# I2C_Switch.net
KiCad netlist of a schematic drawn in Altium Designer
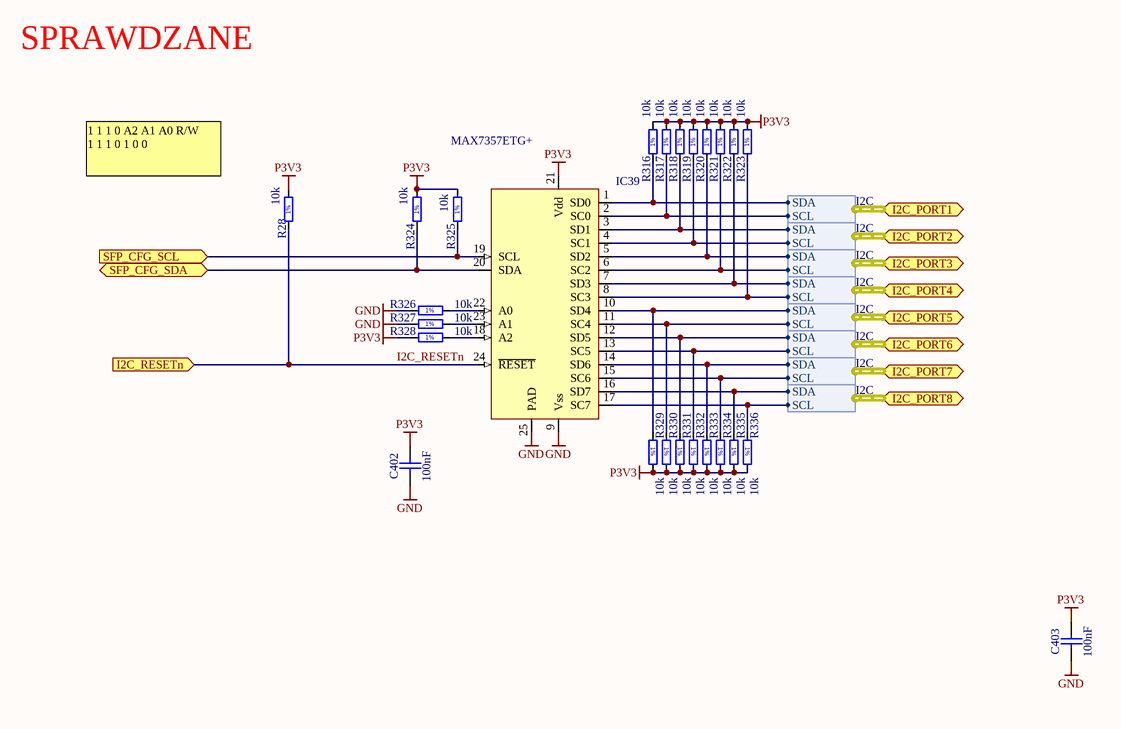
[diagram p0: I2C_Switch.SchDoc]

(export (version "E")
  (design (tool "Eeschema 10.0.6"))
  (components
    (comp (ref "C402")
      (value "100nF")
      (footprint "CAPC0603X33N")
      (description "Non-polarised capacitor")
      (fields
        (field (name "PART NUMBER") "CC0201_100NF_6.3V_10%_X5R")
        (field (name "VOLTAGE") "6.3V")
        (field (name "AUTHOR") "CERN DEM JLC")
      )
      (libsource (lib "Capacitors") (part "Capacitor - non polarized"))
    )
    (comp (ref "C403")
      (value "100nF")
      (footprint "CAPC0603X33N")
      (description "Non-polarised capacitor")
      (fields
        (field (name "PART NUMBER") "CC0201_100NF_6.3V_10%_X5R")
        (field (name "VOLTAGE") "6.3V")
        (field (name "AUTHOR") "CERN DEM JLC")
      )
      (libsource (lib "Capacitors") (part "Capacitor - non polarized"))
    )
    (comp (ref "IC39")
      (value "MAX7357ETG+")
      (footprint "HVQFN24")
      (description "8-channel I2C-bus multiplexer with reset, INT and timeout")
      (libsource (lib "LIBRARY_SCH") (part "IIC_MUX_MAX7357ETG+"))
    )
    (comp (ref "R28")
      (value "10k")
      (footprint "RESC1005X40N")
      (description "Resistor - 1%")
      (fields
        (field (name "PART NUMBER") "R0402_10K_1%_0.0625W_100PPM")
        (field (name "POWER") "0.0625W")
        (field (name "AUTHOR") "CERN DEM JLC")
      )
      (libsource (lib "Resistors") (part "Resistor - 1%"))
    )
    (comp (ref "R316")
      (value "10k")
      (footprint "RESC1005X40N")
      (description "Resistor - 1%")
      (fields
        (field (name "PART NUMBER") "R0402_10K_1%_0.0625W_100PPM")
        (field (name "POWER") "0.0625W")
        (field (name "AUTHOR") "CERN DEM JLC")
      )
      (libsource (lib "Resistors") (part "Resistor - 1%"))
    )
    (comp (ref "R317")
      (value "10k")
      (footprint "RESC1005X40N")
      (description "Resistor - 1%")
      (fields
        (field (name "PART NUMBER") "R0402_10K_1%_0.0625W_100PPM")
        (field (name "POWER") "0.0625W")
        (field (name "AUTHOR") "CERN DEM JLC")
      )
      (libsource (lib "Resistors") (part "Resistor - 1%"))
    )
    (comp (ref "R318")
      (value "10k")
      (footprint "RESC1005X40N")
      (description "Resistor - 1%")
      (fields
        (field (name "PART NUMBER") "R0402_10K_1%_0.0625W_100PPM")
        (field (name "POWER") "0.0625W")
        (field (name "AUTHOR") "CERN DEM JLC")
      )
      (libsource (lib "Resistors") (part "Resistor - 1%"))
    )
    (comp (ref "R319")
      (value "10k")
      (footprint "RESC1005X40N")
      (description "Resistor - 1%")
      (fields
        (field (name "PART NUMBER") "R0402_10K_1%_0.0625W_100PPM")
        (field (name "POWER") "0.0625W")
        (field (name "AUTHOR") "CERN DEM JLC")
      )
      (libsource (lib "Resistors") (part "Resistor - 1%"))
    )
    (comp (ref "R320")
      (value "10k")
      (footprint "RESC1005X40N")
      (description "Resistor - 1%")
      (fields
        (field (name "PART NUMBER") "R0402_10K_1%_0.0625W_100PPM")
        (field (name "POWER") "0.0625W")
        (field (name "AUTHOR") "CERN DEM JLC")
      )
      (libsource (lib "Resistors") (part "Resistor - 1%"))
    )
    (comp (ref "R321")
      (value "10k")
      (footprint "RESC1005X40N")
      (description "Resistor - 1%")
      (fields
        (field (name "PART NUMBER") "R0402_10K_1%_0.0625W_100PPM")
        (field (name "POWER") "0.0625W")
        (field (name "AUTHOR") "CERN DEM JLC")
      )
      (libsource (lib "Resistors") (part "Resistor - 1%"))
    )
    (comp (ref "R322")
      (value "10k")
      (footprint "RESC1005X40N")
      (description "Resistor - 1%")
      (fields
        (field (name "PART NUMBER") "R0402_10K_1%_0.0625W_100PPM")
        (field (name "POWER") "0.0625W")
        (field (name "AUTHOR") "CERN DEM JLC")
      )
      (libsource (lib "Resistors") (part "Resistor - 1%"))
    )
    (comp (ref "R323")
      (value "10k")
      (footprint "RESC1005X40N")
      (description "Resistor - 1%")
      (fields
        (field (name "PART NUMBER") "R0402_10K_1%_0.0625W_100PPM")
        (field (name "POWER") "0.0625W")
        (field (name "AUTHOR") "CERN DEM JLC")
      )
      (libsource (lib "Resistors") (part "Resistor - 1%"))
    )
    (comp (ref "R324")
      (value "10k")
      (footprint "RESC1005X40N")
      (description "Resistor - 1%")
      (fields
        (field (name "PART NUMBER") "R0402_10K_1%_0.0625W_100PPM")
        (field (name "POWER") "0.0625W")
        (field (name "AUTHOR") "CERN DEM JLC")
      )
      (libsource (lib "Resistors") (part "Resistor - 1%"))
    )
    (comp (ref "R325")
      (value "10k")
      (footprint "RESC1005X40N")
      (description "Resistor - 1%")
      (fields
        (field (name "PART NUMBER") "R0402_10K_1%_0.0625W_100PPM")
        (field (name "POWER") "0.0625W")
        (field (name "AUTHOR") "CERN DEM JLC")
      )
      (libsource (lib "Resistors") (part "Resistor - 1%"))
    )
    (comp (ref "R326")
      (value "10k")
      (footprint "RESC1005X40N")
      (description "Resistor - 1%")
      (fields
        (field (name "PART NUMBER") "R0402_10K_1%_0.0625W_100PPM")
        (field (name "POWER") "0.0625W")
        (field (name "AUTHOR") "CERN DEM JLC")
      )
      (libsource (lib "Resistors") (part "Resistor - 1%"))
    )
    (comp (ref "R327")
      (value "10k")
      (footprint "RESC1005X40N")
      (description "Resistor - 1%")
      (fields
        (field (name "PART NUMBER") "R0402_10K_1%_0.0625W_100PPM")
        (field (name "POWER") "0.0625W")
        (field (name "AUTHOR") "CERN DEM JLC")
      )
      (libsource (lib "Resistors") (part "Resistor - 1%"))
    )
    (comp (ref "R328")
      (value "10k")
      (footprint "RESC1005X40N")
      (description "Resistor - 1%")
      (fields
        (field (name "PART NUMBER") "R0402_10K_1%_0.0625W_100PPM")
        (field (name "POWER") "0.0625W")
        (field (name "AUTHOR") "CERN DEM JLC")
      )
      (libsource (lib "Resistors") (part "Resistor - 1%"))
    )
    (comp (ref "R329")
      (value "10k")
      (footprint "RESC1005X40N")
      (description "Resistor - 1%")
      (fields
        (field (name "PART NUMBER") "R0402_10K_1%_0.0625W_100PPM")
        (field (name "POWER") "0.0625W")
        (field (name "AUTHOR") "CERN DEM JLC")
      )
      (libsource (lib "Resistors") (part "Resistor - 1%"))
    )
    (comp (ref "R330")
      (value "10k")
      (footprint "RESC1005X40N")
      (description "Resistor - 1%")
      (fields
        (field (name "PART NUMBER") "R0402_10K_1%_0.0625W_100PPM")
        (field (name "POWER") "0.0625W")
        (field (name "AUTHOR") "CERN DEM JLC")
      )
      (libsource (lib "Resistors") (part "Resistor - 1%"))
    )
    (comp (ref "R331")
      (value "10k")
      (footprint "RESC1005X40N")
      (description "Resistor - 1%")
      (fields
        (field (name "PART NUMBER") "R0402_10K_1%_0.0625W_100PPM")
        (field (name "POWER") "0.0625W")
        (field (name "AUTHOR") "CERN DEM JLC")
      )
      (libsource (lib "Resistors") (part "Resistor - 1%"))
    )
    (comp (ref "R332")
      (value "10k")
      (footprint "RESC1005X40N")
      (description "Resistor - 1%")
      (fields
        (field (name "PART NUMBER") "R0402_10K_1%_0.0625W_100PPM")
        (field (name "POWER") "0.0625W")
        (field (name "AUTHOR") "CERN DEM JLC")
      )
      (libsource (lib "Resistors") (part "Resistor - 1%"))
    )
    (comp (ref "R333")
      (value "10k")
      (footprint "RESC1005X40N")
      (description "Resistor - 1%")
      (fields
        (field (name "PART NUMBER") "R0402_10K_1%_0.0625W_100PPM")
        (field (name "POWER") "0.0625W")
        (field (name "AUTHOR") "CERN DEM JLC")
      )
      (libsource (lib "Resistors") (part "Resistor - 1%"))
    )
    (comp (ref "R334")
      (value "10k")
      (footprint "RESC1005X40N")
      (description "Resistor - 1%")
      (fields
        (field (name "PART NUMBER") "R0402_10K_1%_0.0625W_100PPM")
        (field (name "POWER") "0.0625W")
        (field (name "AUTHOR") "CERN DEM JLC")
      )
      (libsource (lib "Resistors") (part "Resistor - 1%"))
    )
    (comp (ref "R335")
      (value "10k")
      (footprint "RESC1005X40N")
      (description "Resistor - 1%")
      (fields
        (field (name "PART NUMBER") "R0402_10K_1%_0.0625W_100PPM")
        (field (name "POWER") "0.0625W")
        (field (name "AUTHOR") "CERN DEM JLC")
      )
      (libsource (lib "Resistors") (part "Resistor - 1%"))
    )
    (comp (ref "R336")
      (value "10k")
      (footprint "RESC1005X40N")
      (description "Resistor - 1%")
      (fields
        (field (name "PART NUMBER") "R0402_10K_1%_0.0625W_100PPM")
        (field (name "POWER") "0.0625W")
        (field (name "AUTHOR") "CERN DEM JLC")
      )
      (libsource (lib "Resistors") (part "Resistor - 1%"))
    )
  )
  (nets
    (net (code "4") (name "/I2C_RESETn") (class "Default")
      (node (ref "IC39") (pin "24") (pinfunction "~{RESET}_24") (pintype "input"))
      (node (ref "R28") (pin "1") (pinfunction "1_1") (pintype "passive"))
    )
    (net (code "5") (name "/SFP_CFG_SCL") (class "Default")
      (node (ref "IC39") (pin "19") (pinfunction "SCL_19") (pintype "input"))
      (node (ref "R325") (pin "1") (pinfunction "1_1") (pintype "passive"))
    )
    (net (code "6") (name "/SFP_CFG_SDA") (class "Default")
      (node (ref "IC39") (pin "20") (pinfunction "SDA_20") (pintype "bidirectional"))
      (node (ref "R324") (pin "1") (pinfunction "1_1") (pintype "passive"))
    )
    (net (code "8") (name "GND") (class "Default")
      (node (ref "C402") (pin "1") (pinfunction "1_1") (pintype "passive"))
      (node (ref "C403") (pin "1") (pinfunction "1_1") (pintype "passive"))
      (node (ref "IC39") (pin "25") (pinfunction "PAD_25") (pintype "power_in"))
      (node (ref "IC39") (pin "9") (pinfunction "Vss_9") (pintype "power_in"))
      (node (ref "R326") (pin "1") (pinfunction "1_1") (pintype "passive"))
      (node (ref "R327") (pin "1") (pinfunction "1_1") (pintype "passive"))
    )
    (net (code "9") (name "Net-(IC39-A0)") (class "Default")
      (node (ref "IC39") (pin "22") (pinfunction "A0_22") (pintype "input"))
      (node (ref "R326") (pin "2") (pinfunction "2_2") (pintype "passive"))
    )
    (net (code "10") (name "Net-(IC39-A1)") (class "Default")
      (node (ref "IC39") (pin "23") (pinfunction "A1_23") (pintype "input"))
      (node (ref "R327") (pin "2") (pinfunction "2_2") (pintype "passive"))
    )
    (net (code "11") (name "Net-(IC39-A2)") (class "Default")
      (node (ref "IC39") (pin "18") (pinfunction "A2_18") (pintype "input"))
      (node (ref "R328") (pin "2") (pinfunction "2_2") (pintype "passive"))
    )
    (net (code "12") (name "Net-(IC39-SC0)") (class "Default")
      (node (ref "IC39") (pin "2") (pinfunction "SC0_2") (pintype "bidirectional"))
      (node (ref "R317") (pin "1") (pinfunction "1_1") (pintype "passive"))
    )
    (net (code "13") (name "Net-(IC39-SC1)") (class "Default")
      (node (ref "IC39") (pin "4") (pinfunction "SC1_4") (pintype "bidirectional"))
      (node (ref "R319") (pin "1") (pinfunction "1_1") (pintype "passive"))
    )
    (net (code "14") (name "Net-(IC39-SC2)") (class "Default")
      (node (ref "IC39") (pin "6") (pinfunction "SC2_6") (pintype "bidirectional"))
      (node (ref "R321") (pin "1") (pinfunction "1_1") (pintype "passive"))
    )
    (net (code "15") (name "Net-(IC39-SC3)") (class "Default")
      (node (ref "IC39") (pin "8") (pinfunction "SC3_8") (pintype "bidirectional"))
      (node (ref "R323") (pin "1") (pinfunction "1_1") (pintype "passive"))
    )
    (net (code "16") (name "Net-(IC39-SC4)") (class "Default")
      (node (ref "IC39") (pin "11") (pinfunction "SC4_11") (pintype "bidirectional"))
      (node (ref "R330") (pin "1") (pinfunction "1_1") (pintype "passive"))
    )
    (net (code "17") (name "Net-(IC39-SC5)") (class "Default")
      (node (ref "IC39") (pin "13") (pinfunction "SC5_13") (pintype "bidirectional"))
      (node (ref "R332") (pin "1") (pinfunction "1_1") (pintype "passive"))
    )
    (net (code "18") (name "Net-(IC39-SC6)") (class "Default")
      (node (ref "IC39") (pin "15") (pinfunction "SC6_15") (pintype "bidirectional"))
      (node (ref "R334") (pin "1") (pinfunction "1_1") (pintype "passive"))
    )
    (net (code "19") (name "Net-(IC39-SC7)") (class "Default")
      (node (ref "IC39") (pin "17") (pinfunction "SC7_17") (pintype "bidirectional"))
      (node (ref "R336") (pin "1") (pinfunction "1_1") (pintype "passive"))
    )
    (net (code "20") (name "Net-(IC39-SD0)") (class "Default")
      (node (ref "IC39") (pin "1") (pinfunction "SD0_1") (pintype "bidirectional"))
      (node (ref "R316") (pin "1") (pinfunction "1_1") (pintype "passive"))
    )
    (net (code "21") (name "Net-(IC39-SD1)") (class "Default")
      (node (ref "IC39") (pin "3") (pinfunction "SD1_3") (pintype "bidirectional"))
      (node (ref "R318") (pin "1") (pinfunction "1_1") (pintype "passive"))
    )
    (net (code "22") (name "Net-(IC39-SD2)") (class "Default")
      (node (ref "IC39") (pin "5") (pinfunction "SD2_5") (pintype "bidirectional"))
      (node (ref "R320") (pin "1") (pinfunction "1_1") (pintype "passive"))
    )
    (net (code "23") (name "Net-(IC39-SD3)") (class "Default")
      (node (ref "IC39") (pin "7") (pinfunction "SD3_7") (pintype "bidirectional"))
      (node (ref "R322") (pin "1") (pinfunction "1_1") (pintype "passive"))
    )
    (net (code "24") (name "Net-(IC39-SD4)") (class "Default")
      (node (ref "IC39") (pin "10") (pinfunction "SD4_10") (pintype "bidirectional"))
      (node (ref "R329") (pin "1") (pinfunction "1_1") (pintype "passive"))
    )
    (net (code "25") (name "Net-(IC39-SD5)") (class "Default")
      (node (ref "IC39") (pin "12") (pinfunction "SD5_12") (pintype "bidirectional"))
      (node (ref "R331") (pin "1") (pinfunction "1_1") (pintype "passive"))
    )
    (net (code "26") (name "Net-(IC39-SD6)") (class "Default")
      (node (ref "IC39") (pin "14") (pinfunction "SD6_14") (pintype "bidirectional"))
      (node (ref "R333") (pin "1") (pinfunction "1_1") (pintype "passive"))
    )
    (net (code "27") (name "Net-(IC39-SD7)") (class "Default")
      (node (ref "IC39") (pin "16") (pinfunction "SD7_16") (pintype "bidirectional"))
      (node (ref "R335") (pin "1") (pinfunction "1_1") (pintype "passive"))
    )
    (net (code "28") (name "P3V3") (class "Default")
      (node (ref "C402") (pin "2") (pinfunction "2_2") (pintype "passive"))
      (node (ref "C403") (pin "2") (pinfunction "2_2") (pintype "passive"))
      (node (ref "IC39") (pin "21") (pinfunction "Vdd_21") (pintype "power_in"))
      (node (ref "R28") (pin "2") (pinfunction "2_2") (pintype "passive"))
      (node (ref "R316") (pin "2") (pinfunction "2_2") (pintype "passive"))
      (node (ref "R317") (pin "2") (pinfunction "2_2") (pintype "passive"))
      (node (ref "R318") (pin "2") (pinfunction "2_2") (pintype "passive"))
      (node (ref "R319") (pin "2") (pinfunction "2_2") (pintype "passive"))
      (node (ref "R320") (pin "2") (pinfunction "2_2") (pintype "passive"))
      (node (ref "R321") (pin "2") (pinfunction "2_2") (pintype "passive"))
      (node (ref "R322") (pin "2") (pinfunction "2_2") (pintype "passive"))
      (node (ref "R323") (pin "2") (pinfunction "2_2") (pintype "passive"))
      (node (ref "R324") (pin "2") (pinfunction "2_2") (pintype "passive"))
      (node (ref "R325") (pin "2") (pinfunction "2_2") (pintype "passive"))
      (node (ref "R328") (pin "1") (pinfunction "1_1") (pintype "passive"))
      (node (ref "R329") (pin "2") (pinfunction "2_2") (pintype "passive"))
      (node (ref "R330") (pin "2") (pinfunction "2_2") (pintype "passive"))
      (node (ref "R331") (pin "2") (pinfunction "2_2") (pintype "passive"))
      (node (ref "R332") (pin "2") (pinfunction "2_2") (pintype "passive"))
      (node (ref "R333") (pin "2") (pinfunction "2_2") (pintype "passive"))
      (node (ref "R334") (pin "2") (pinfunction "2_2") (pintype "passive"))
      (node (ref "R335") (pin "2") (pinfunction "2_2") (pintype "passive"))
      (node (ref "R336") (pin "2") (pinfunction "2_2") (pintype "passive"))
    )
  )
)
